# Pai_zhen_Pin.net
KiCad netlist of a schematic drawn in EasyEDA Pro
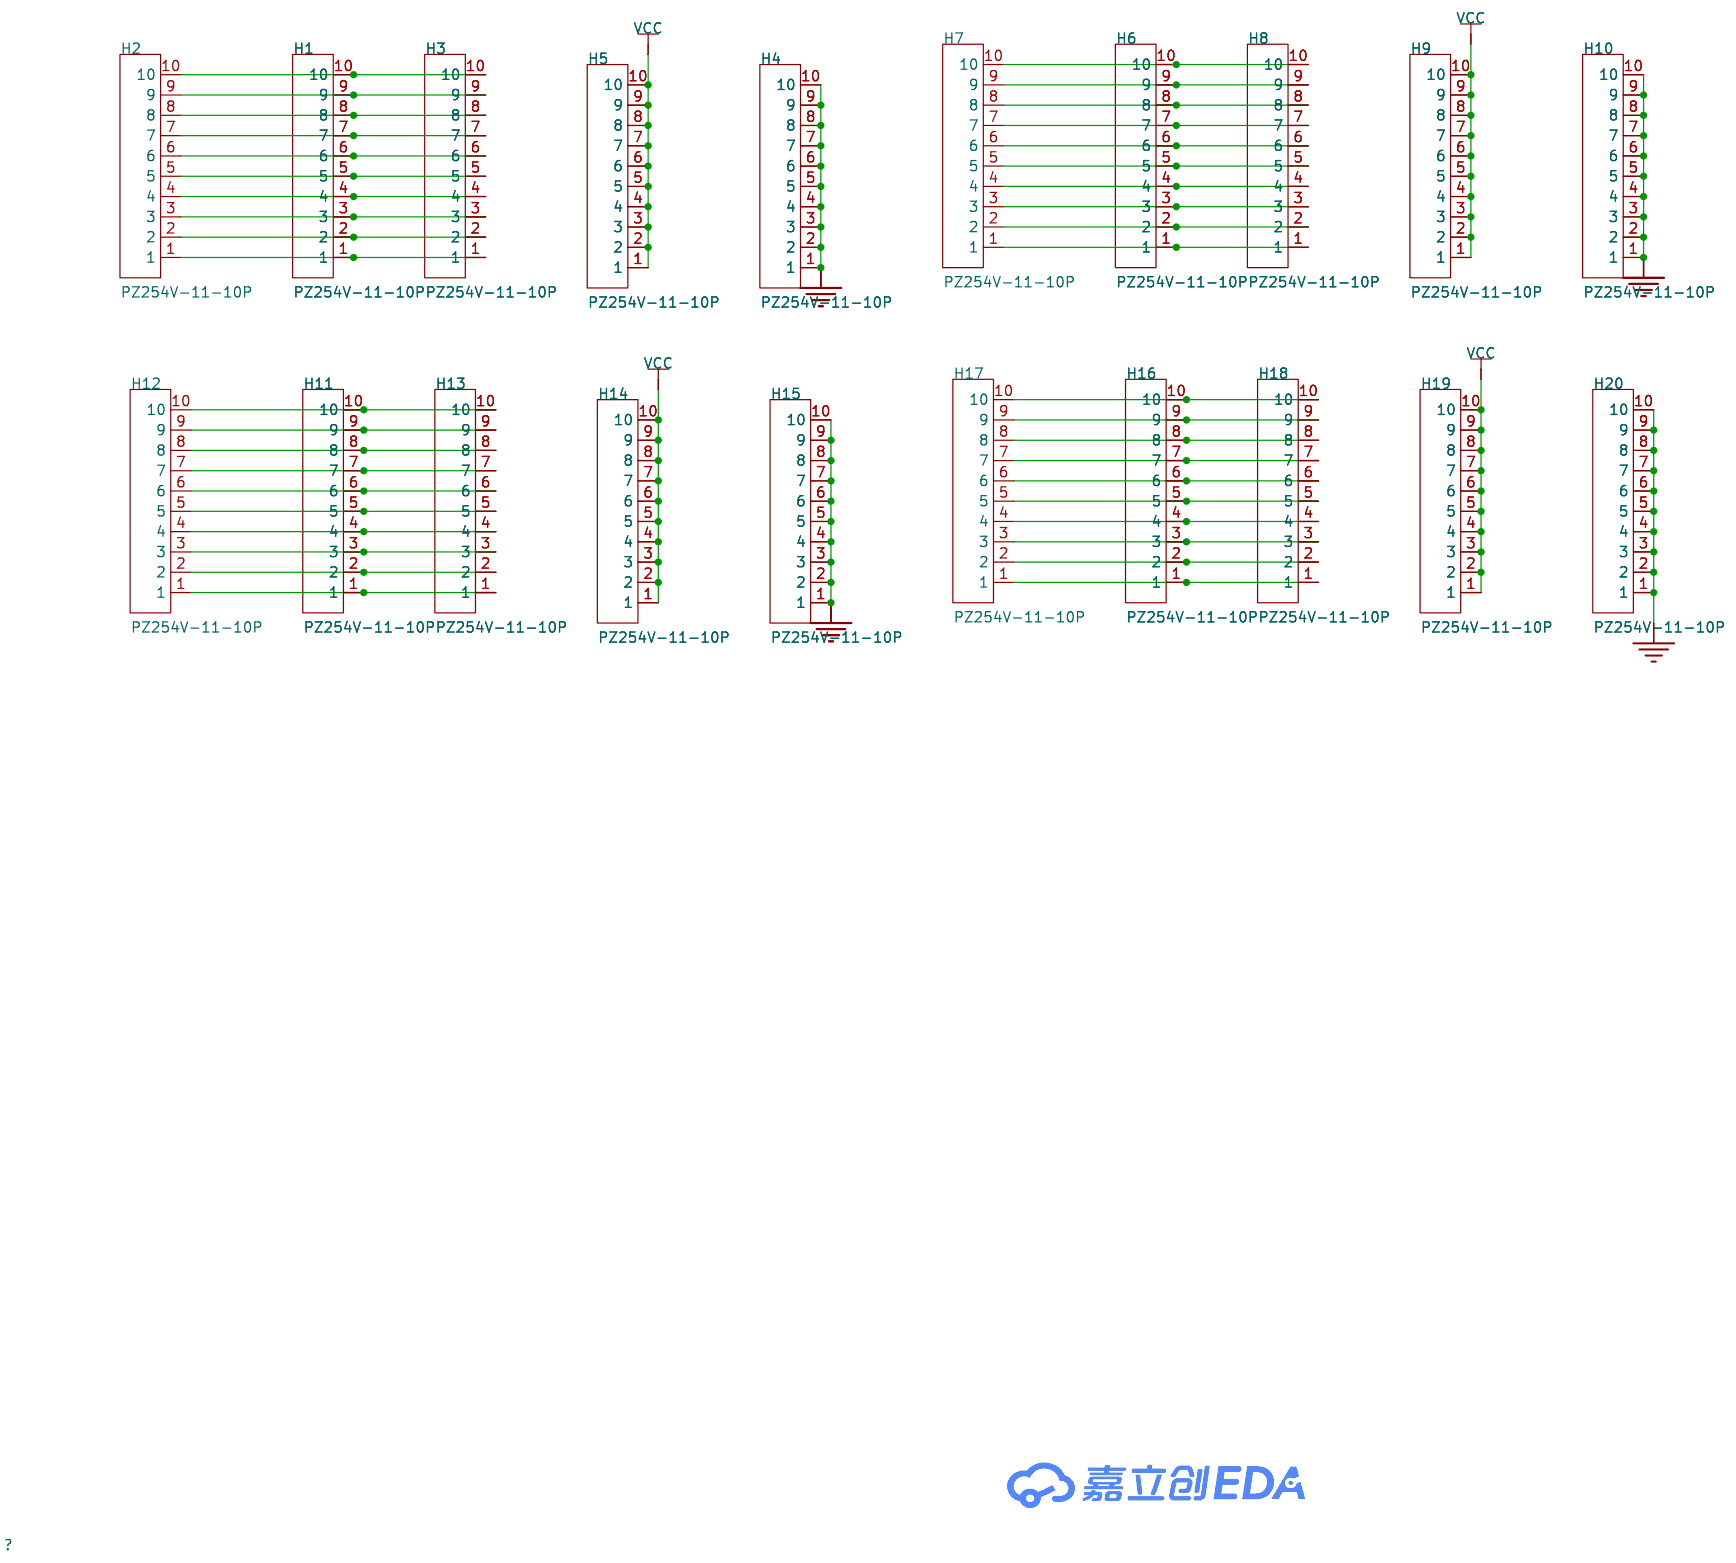
[diagram p0: schematic sheet]

(export (version "E")
  (design (tool "Eeschema 10.0.6"))
  (components
    (comp (ref "H1")
      (value "PZ254V-11-10P")
      (footprint "easyedapro:HDR-TH_10P-P2.54-V-M")
      (fields (field (name "Manufacturer") "XFCN(兴飞)"))
      (libsource (lib "easyedapro") (part "PZ254V-11-10P"))
    )
    (comp (ref "H2")
      (value "PZ254V-11-10P")
      (footprint "easyedapro:HDR-TH_10P-P2.54-V-M")
      (fields (field (name "Manufacturer") "XFCN(兴飞)"))
      (libsource (lib "easyedapro") (part "PZ254V-11-10P"))
    )
    (comp (ref "H3")
      (value "PZ254V-11-10P")
      (footprint "easyedapro:HDR-TH_10P-P2.54-V-M")
      (fields (field (name "Manufacturer") "XFCN(兴飞)"))
      (libsource (lib "easyedapro") (part "PZ254V-11-10P"))
    )
    (comp (ref "H4")
      (value "PZ254V-11-10P")
      (footprint "easyedapro:HDR-TH_10P-P2.54-V-M")
      (fields (field (name "Manufacturer") "XFCN(兴飞)"))
      (libsource (lib "easyedapro") (part "PZ254V-11-10P"))
    )
    (comp (ref "H5")
      (value "PZ254V-11-10P")
      (footprint "easyedapro:HDR-TH_10P-P2.54-V-M")
      (fields (field (name "Manufacturer") "XFCN(兴飞)"))
      (libsource (lib "easyedapro") (part "PZ254V-11-10P"))
    )
    (comp (ref "H6")
      (value "PZ254V-11-10P")
      (footprint "easyedapro:HDR-TH_10P-P2.54-V-M")
      (fields (field (name "Manufacturer") "XFCN(兴飞)"))
      (libsource (lib "easyedapro") (part "PZ254V-11-10P"))
    )
    (comp (ref "H7")
      (value "PZ254V-11-10P")
      (footprint "easyedapro:HDR-TH_10P-P2.54-V-M")
      (fields (field (name "Manufacturer") "XFCN(兴飞)"))
      (libsource (lib "easyedapro") (part "PZ254V-11-10P"))
    )
    (comp (ref "H8")
      (value "PZ254V-11-10P")
      (footprint "easyedapro:HDR-TH_10P-P2.54-V-M")
      (fields (field (name "Manufacturer") "XFCN(兴飞)"))
      (libsource (lib "easyedapro") (part "PZ254V-11-10P"))
    )
    (comp (ref "H9")
      (value "PZ254V-11-10P")
      (footprint "easyedapro:HDR-TH_10P-P2.54-V-M")
      (fields (field (name "Manufacturer") "XFCN(兴飞)"))
      (libsource (lib "easyedapro") (part "PZ254V-11-10P"))
    )
    (comp (ref "H10")
      (value "PZ254V-11-10P")
      (footprint "easyedapro:HDR-TH_10P-P2.54-V-M")
      (fields (field (name "Manufacturer") "XFCN(兴飞)"))
      (libsource (lib "easyedapro") (part "PZ254V-11-10P"))
    )
    (comp (ref "H11")
      (value "PZ254V-11-10P")
      (footprint "easyedapro:HDR-TH_10P-P2.54-V-M")
      (fields (field (name "Manufacturer") "XFCN(兴飞)"))
      (libsource (lib "easyedapro") (part "PZ254V-11-10P"))
    )
    (comp (ref "H12")
      (value "PZ254V-11-10P")
      (footprint "easyedapro:HDR-TH_10P-P2.54-V-M")
      (fields (field (name "Manufacturer") "XFCN(兴飞)"))
      (libsource (lib "easyedapro") (part "PZ254V-11-10P"))
    )
    (comp (ref "H13")
      (value "PZ254V-11-10P")
      (footprint "easyedapro:HDR-TH_10P-P2.54-V-M")
      (fields (field (name "Manufacturer") "XFCN(兴飞)"))
      (libsource (lib "easyedapro") (part "PZ254V-11-10P"))
    )
    (comp (ref "H14")
      (value "PZ254V-11-10P")
      (footprint "easyedapro:HDR-TH_10P-P2.54-V-M")
      (fields (field (name "Manufacturer") "XFCN(兴飞)"))
      (libsource (lib "easyedapro") (part "PZ254V-11-10P"))
    )
    (comp (ref "H15")
      (value "PZ254V-11-10P")
      (footprint "easyedapro:HDR-TH_10P-P2.54-V-M")
      (fields (field (name "Manufacturer") "XFCN(兴飞)"))
      (libsource (lib "easyedapro") (part "PZ254V-11-10P"))
    )
    (comp (ref "H16")
      (value "PZ254V-11-10P")
      (footprint "easyedapro:HDR-TH_10P-P2.54-V-M")
      (fields (field (name "Manufacturer") "XFCN(兴飞)"))
      (libsource (lib "easyedapro") (part "PZ254V-11-10P"))
    )
    (comp (ref "H17")
      (value "PZ254V-11-10P")
      (footprint "easyedapro:HDR-TH_10P-P2.54-V-M")
      (fields (field (name "Manufacturer") "XFCN(兴飞)"))
      (libsource (lib "easyedapro") (part "PZ254V-11-10P"))
    )
    (comp (ref "H18")
      (value "PZ254V-11-10P")
      (footprint "easyedapro:HDR-TH_10P-P2.54-V-M")
      (fields (field (name "Manufacturer") "XFCN(兴飞)"))
      (libsource (lib "easyedapro") (part "PZ254V-11-10P"))
    )
    (comp (ref "H19")
      (value "PZ254V-11-10P")
      (footprint "easyedapro:HDR-TH_10P-P2.54-V-M")
      (fields (field (name "Manufacturer") "XFCN(兴飞)"))
      (libsource (lib "easyedapro") (part "PZ254V-11-10P"))
    )
    (comp (ref "H20")
      (value "PZ254V-11-10P")
      (footprint "easyedapro:HDR-TH_10P-P2.54-V-M")
      (fields (field (name "Manufacturer") "XFCN(兴飞)"))
      (libsource (lib "easyedapro") (part "PZ254V-11-10P"))
    )
  )
  (nets
    (net (code "1") (name "GND") (class "Default")
      (node (ref "H10") (pin "1") (pinfunction "1_1") (pintype "unspecified"))
      (node (ref "H10") (pin "10") (pinfunction "10_10") (pintype "unspecified"))
      (node (ref "H10") (pin "2") (pinfunction "2_2") (pintype "unspecified"))
      (node (ref "H10") (pin "3") (pinfunction "3_3") (pintype "unspecified"))
      (node (ref "H10") (pin "4") (pinfunction "4_4") (pintype "unspecified"))
      (node (ref "H10") (pin "5") (pinfunction "5_5") (pintype "unspecified"))
      (node (ref "H10") (pin "6") (pinfunction "6_6") (pintype "unspecified"))
      (node (ref "H10") (pin "7") (pinfunction "7_7") (pintype "unspecified"))
      (node (ref "H10") (pin "8") (pinfunction "8_8") (pintype "unspecified"))
      (node (ref "H10") (pin "9") (pinfunction "9_9") (pintype "unspecified"))
      (node (ref "H15") (pin "1") (pinfunction "1_1") (pintype "unspecified"))
      (node (ref "H15") (pin "10") (pinfunction "10_10") (pintype "unspecified"))
      (node (ref "H15") (pin "2") (pinfunction "2_2") (pintype "unspecified"))
      (node (ref "H15") (pin "3") (pinfunction "3_3") (pintype "unspecified"))
      (node (ref "H15") (pin "4") (pinfunction "4_4") (pintype "unspecified"))
      (node (ref "H15") (pin "5") (pinfunction "5_5") (pintype "unspecified"))
      (node (ref "H15") (pin "6") (pinfunction "6_6") (pintype "unspecified"))
      (node (ref "H15") (pin "7") (pinfunction "7_7") (pintype "unspecified"))
      (node (ref "H15") (pin "8") (pinfunction "8_8") (pintype "unspecified"))
      (node (ref "H15") (pin "9") (pinfunction "9_9") (pintype "unspecified"))
      (node (ref "H20") (pin "1") (pinfunction "1_1") (pintype "unspecified"))
      (node (ref "H20") (pin "10") (pinfunction "10_10") (pintype "unspecified"))
      (node (ref "H20") (pin "2") (pinfunction "2_2") (pintype "unspecified"))
      (node (ref "H20") (pin "3") (pinfunction "3_3") (pintype "unspecified"))
      (node (ref "H20") (pin "4") (pinfunction "4_4") (pintype "unspecified"))
      (node (ref "H20") (pin "5") (pinfunction "5_5") (pintype "unspecified"))
      (node (ref "H20") (pin "6") (pinfunction "6_6") (pintype "unspecified"))
      (node (ref "H20") (pin "7") (pinfunction "7_7") (pintype "unspecified"))
      (node (ref "H20") (pin "8") (pinfunction "8_8") (pintype "unspecified"))
      (node (ref "H20") (pin "9") (pinfunction "9_9") (pintype "unspecified"))
      (node (ref "H4") (pin "1") (pinfunction "1_1") (pintype "unspecified"))
      (node (ref "H4") (pin "10") (pinfunction "10_10") (pintype "unspecified"))
      (node (ref "H4") (pin "2") (pinfunction "2_2") (pintype "unspecified"))
      (node (ref "H4") (pin "3") (pinfunction "3_3") (pintype "unspecified"))
      (node (ref "H4") (pin "4") (pinfunction "4_4") (pintype "unspecified"))
      (node (ref "H4") (pin "5") (pinfunction "5_5") (pintype "unspecified"))
      (node (ref "H4") (pin "6") (pinfunction "6_6") (pintype "unspecified"))
      (node (ref "H4") (pin "7") (pinfunction "7_7") (pintype "unspecified"))
      (node (ref "H4") (pin "8") (pinfunction "8_8") (pintype "unspecified"))
      (node (ref "H4") (pin "9") (pinfunction "9_9") (pintype "unspecified"))
    )
    (net (code "2") (name "Net-(H1-Pad1)") (class "Default")
      (node (ref "H1") (pin "1") (pinfunction "1_1") (pintype "unspecified"))
      (node (ref "H2") (pin "1") (pinfunction "1_1") (pintype "unspecified"))
      (node (ref "H3") (pin "1") (pinfunction "1_1") (pintype "unspecified"))
    )
    (net (code "3") (name "Net-(H1-Pad2)") (class "Default")
      (node (ref "H1") (pin "2") (pinfunction "2_2") (pintype "unspecified"))
      (node (ref "H2") (pin "2") (pinfunction "2_2") (pintype "unspecified"))
      (node (ref "H3") (pin "2") (pinfunction "2_2") (pintype "unspecified"))
    )
    (net (code "4") (name "Net-(H1-Pad3)") (class "Default")
      (node (ref "H1") (pin "3") (pinfunction "3_3") (pintype "unspecified"))
      (node (ref "H2") (pin "3") (pinfunction "3_3") (pintype "unspecified"))
      (node (ref "H3") (pin "3") (pinfunction "3_3") (pintype "unspecified"))
    )
    (net (code "5") (name "Net-(H1-Pad4)") (class "Default")
      (node (ref "H1") (pin "4") (pinfunction "4_4") (pintype "unspecified"))
      (node (ref "H2") (pin "4") (pinfunction "4_4") (pintype "unspecified"))
      (node (ref "H3") (pin "4") (pinfunction "4_4") (pintype "unspecified"))
    )
    (net (code "6") (name "Net-(H1-Pad5)") (class "Default")
      (node (ref "H1") (pin "5") (pinfunction "5_5") (pintype "unspecified"))
      (node (ref "H2") (pin "5") (pinfunction "5_5") (pintype "unspecified"))
      (node (ref "H3") (pin "5") (pinfunction "5_5") (pintype "unspecified"))
    )
    (net (code "7") (name "Net-(H1-Pad6)") (class "Default")
      (node (ref "H1") (pin "6") (pinfunction "6_6") (pintype "unspecified"))
      (node (ref "H2") (pin "6") (pinfunction "6_6") (pintype "unspecified"))
      (node (ref "H3") (pin "6") (pinfunction "6_6") (pintype "unspecified"))
    )
    (net (code "8") (name "Net-(H1-Pad7)") (class "Default")
      (node (ref "H1") (pin "7") (pinfunction "7_7") (pintype "unspecified"))
      (node (ref "H2") (pin "7") (pinfunction "7_7") (pintype "unspecified"))
      (node (ref "H3") (pin "7") (pinfunction "7_7") (pintype "unspecified"))
    )
    (net (code "9") (name "Net-(H1-Pad8)") (class "Default")
      (node (ref "H1") (pin "8") (pinfunction "8_8") (pintype "unspecified"))
      (node (ref "H2") (pin "8") (pinfunction "8_8") (pintype "unspecified"))
      (node (ref "H3") (pin "8") (pinfunction "8_8") (pintype "unspecified"))
    )
    (net (code "10") (name "Net-(H1-Pad9)") (class "Default")
      (node (ref "H1") (pin "9") (pinfunction "9_9") (pintype "unspecified"))
      (node (ref "H2") (pin "9") (pinfunction "9_9") (pintype "unspecified"))
      (node (ref "H3") (pin "9") (pinfunction "9_9") (pintype "unspecified"))
    )
    (net (code "11") (name "Net-(H1-Pad10)") (class "Default")
      (node (ref "H1") (pin "10") (pinfunction "10_10") (pintype "unspecified"))
      (node (ref "H2") (pin "10") (pinfunction "10_10") (pintype "unspecified"))
      (node (ref "H3") (pin "10") (pinfunction "10_10") (pintype "unspecified"))
    )
    (net (code "12") (name "Net-(H6-Pad1)") (class "Default")
      (node (ref "H6") (pin "1") (pinfunction "1_1") (pintype "unspecified"))
      (node (ref "H7") (pin "1") (pinfunction "1_1") (pintype "unspecified"))
      (node (ref "H8") (pin "1") (pinfunction "1_1") (pintype "unspecified"))
    )
    (net (code "13") (name "Net-(H6-Pad2)") (class "Default")
      (node (ref "H6") (pin "2") (pinfunction "2_2") (pintype "unspecified"))
      (node (ref "H7") (pin "2") (pinfunction "2_2") (pintype "unspecified"))
      (node (ref "H8") (pin "2") (pinfunction "2_2") (pintype "unspecified"))
    )
    (net (code "14") (name "Net-(H6-Pad3)") (class "Default")
      (node (ref "H6") (pin "3") (pinfunction "3_3") (pintype "unspecified"))
      (node (ref "H7") (pin "3") (pinfunction "3_3") (pintype "unspecified"))
      (node (ref "H8") (pin "3") (pinfunction "3_3") (pintype "unspecified"))
    )
    (net (code "15") (name "Net-(H6-Pad4)") (class "Default")
      (node (ref "H6") (pin "4") (pinfunction "4_4") (pintype "unspecified"))
      (node (ref "H7") (pin "4") (pinfunction "4_4") (pintype "unspecified"))
      (node (ref "H8") (pin "4") (pinfunction "4_4") (pintype "unspecified"))
    )
    (net (code "16") (name "Net-(H6-Pad5)") (class "Default")
      (node (ref "H6") (pin "5") (pinfunction "5_5") (pintype "unspecified"))
      (node (ref "H7") (pin "5") (pinfunction "5_5") (pintype "unspecified"))
      (node (ref "H8") (pin "5") (pinfunction "5_5") (pintype "unspecified"))
    )
    (net (code "17") (name "Net-(H6-Pad6)") (class "Default")
      (node (ref "H6") (pin "6") (pinfunction "6_6") (pintype "unspecified"))
      (node (ref "H7") (pin "6") (pinfunction "6_6") (pintype "unspecified"))
      (node (ref "H8") (pin "6") (pinfunction "6_6") (pintype "unspecified"))
    )
    (net (code "18") (name "Net-(H6-Pad7)") (class "Default")
      (node (ref "H6") (pin "7") (pinfunction "7_7") (pintype "unspecified"))
      (node (ref "H7") (pin "7") (pinfunction "7_7") (pintype "unspecified"))
      (node (ref "H8") (pin "7") (pinfunction "7_7") (pintype "unspecified"))
    )
    (net (code "19") (name "Net-(H6-Pad8)") (class "Default")
      (node (ref "H6") (pin "8") (pinfunction "8_8") (pintype "unspecified"))
      (node (ref "H7") (pin "8") (pinfunction "8_8") (pintype "unspecified"))
      (node (ref "H8") (pin "8") (pinfunction "8_8") (pintype "unspecified"))
    )
    (net (code "20") (name "Net-(H6-Pad9)") (class "Default")
      (node (ref "H6") (pin "9") (pinfunction "9_9") (pintype "unspecified"))
      (node (ref "H7") (pin "9") (pinfunction "9_9") (pintype "unspecified"))
      (node (ref "H8") (pin "9") (pinfunction "9_9") (pintype "unspecified"))
    )
    (net (code "21") (name "Net-(H6-Pad10)") (class "Default")
      (node (ref "H6") (pin "10") (pinfunction "10_10") (pintype "unspecified"))
      (node (ref "H7") (pin "10") (pinfunction "10_10") (pintype "unspecified"))
      (node (ref "H8") (pin "10") (pinfunction "10_10") (pintype "unspecified"))
    )
    (net (code "22") (name "Net-(H11-Pad1)") (class "Default")
      (node (ref "H11") (pin "1") (pinfunction "1_1") (pintype "unspecified"))
      (node (ref "H12") (pin "1") (pinfunction "1_1") (pintype "unspecified"))
      (node (ref "H13") (pin "1") (pinfunction "1_1") (pintype "unspecified"))
    )
    (net (code "23") (name "Net-(H11-Pad2)") (class "Default")
      (node (ref "H11") (pin "2") (pinfunction "2_2") (pintype "unspecified"))
      (node (ref "H12") (pin "2") (pinfunction "2_2") (pintype "unspecified"))
      (node (ref "H13") (pin "2") (pinfunction "2_2") (pintype "unspecified"))
    )
    (net (code "24") (name "Net-(H11-Pad3)") (class "Default")
      (node (ref "H11") (pin "3") (pinfunction "3_3") (pintype "unspecified"))
      (node (ref "H12") (pin "3") (pinfunction "3_3") (pintype "unspecified"))
      (node (ref "H13") (pin "3") (pinfunction "3_3") (pintype "unspecified"))
    )
    (net (code "25") (name "Net-(H11-Pad4)") (class "Default")
      (node (ref "H11") (pin "4") (pinfunction "4_4") (pintype "unspecified"))
      (node (ref "H12") (pin "4") (pinfunction "4_4") (pintype "unspecified"))
      (node (ref "H13") (pin "4") (pinfunction "4_4") (pintype "unspecified"))
    )
    (net (code "26") (name "Net-(H11-Pad5)") (class "Default")
      (node (ref "H11") (pin "5") (pinfunction "5_5") (pintype "unspecified"))
      (node (ref "H12") (pin "5") (pinfunction "5_5") (pintype "unspecified"))
      (node (ref "H13") (pin "5") (pinfunction "5_5") (pintype "unspecified"))
    )
    (net (code "27") (name "Net-(H11-Pad6)") (class "Default")
      (node (ref "H11") (pin "6") (pinfunction "6_6") (pintype "unspecified"))
      (node (ref "H12") (pin "6") (pinfunction "6_6") (pintype "unspecified"))
      (node (ref "H13") (pin "6") (pinfunction "6_6") (pintype "unspecified"))
    )
    (net (code "28") (name "Net-(H11-Pad7)") (class "Default")
      (node (ref "H11") (pin "7") (pinfunction "7_7") (pintype "unspecified"))
      (node (ref "H12") (pin "7") (pinfunction "7_7") (pintype "unspecified"))
      (node (ref "H13") (pin "7") (pinfunction "7_7") (pintype "unspecified"))
    )
    (net (code "29") (name "Net-(H11-Pad8)") (class "Default")
      (node (ref "H11") (pin "8") (pinfunction "8_8") (pintype "unspecified"))
      (node (ref "H12") (pin "8") (pinfunction "8_8") (pintype "unspecified"))
      (node (ref "H13") (pin "8") (pinfunction "8_8") (pintype "unspecified"))
    )
    (net (code "30") (name "Net-(H11-Pad9)") (class "Default")
      (node (ref "H11") (pin "9") (pinfunction "9_9") (pintype "unspecified"))
      (node (ref "H12") (pin "9") (pinfunction "9_9") (pintype "unspecified"))
      (node (ref "H13") (pin "9") (pinfunction "9_9") (pintype "unspecified"))
    )
    (net (code "31") (name "Net-(H11-Pad10)") (class "Default")
      (node (ref "H11") (pin "10") (pinfunction "10_10") (pintype "unspecified"))
      (node (ref "H12") (pin "10") (pinfunction "10_10") (pintype "unspecified"))
      (node (ref "H13") (pin "10") (pinfunction "10_10") (pintype "unspecified"))
    )
    (net (code "32") (name "Net-(H16-Pad1)") (class "Default")
      (node (ref "H16") (pin "1") (pinfunction "1_1") (pintype "unspecified"))
      (node (ref "H17") (pin "1") (pinfunction "1_1") (pintype "unspecified"))
      (node (ref "H18") (pin "1") (pinfunction "1_1") (pintype "unspecified"))
    )
    (net (code "33") (name "Net-(H16-Pad2)") (class "Default")
      (node (ref "H16") (pin "2") (pinfunction "2_2") (pintype "unspecified"))
      (node (ref "H17") (pin "2") (pinfunction "2_2") (pintype "unspecified"))
      (node (ref "H18") (pin "2") (pinfunction "2_2") (pintype "unspecified"))
    )
    (net (code "34") (name "Net-(H16-Pad3)") (class "Default")
      (node (ref "H16") (pin "3") (pinfunction "3_3") (pintype "unspecified"))
      (node (ref "H17") (pin "3") (pinfunction "3_3") (pintype "unspecified"))
      (node (ref "H18") (pin "3") (pinfunction "3_3") (pintype "unspecified"))
    )
    (net (code "35") (name "Net-(H16-Pad4)") (class "Default")
      (node (ref "H16") (pin "4") (pinfunction "4_4") (pintype "unspecified"))
      (node (ref "H17") (pin "4") (pinfunction "4_4") (pintype "unspecified"))
      (node (ref "H18") (pin "4") (pinfunction "4_4") (pintype "unspecified"))
    )
    (net (code "36") (name "Net-(H16-Pad5)") (class "Default")
      (node (ref "H16") (pin "5") (pinfunction "5_5") (pintype "unspecified"))
      (node (ref "H17") (pin "5") (pinfunction "5_5") (pintype "unspecified"))
      (node (ref "H18") (pin "5") (pinfunction "5_5") (pintype "unspecified"))
    )
    (net (code "37") (name "Net-(H16-Pad6)") (class "Default")
      (node (ref "H16") (pin "6") (pinfunction "6_6") (pintype "unspecified"))
      (node (ref "H17") (pin "6") (pinfunction "6_6") (pintype "unspecified"))
      (node (ref "H18") (pin "6") (pinfunction "6_6") (pintype "unspecified"))
    )
    (net (code "38") (name "Net-(H16-Pad7)") (class "Default")
      (node (ref "H16") (pin "7") (pinfunction "7_7") (pintype "unspecified"))
      (node (ref "H17") (pin "7") (pinfunction "7_7") (pintype "unspecified"))
      (node (ref "H18") (pin "7") (pinfunction "7_7") (pintype "unspecified"))
    )
    (net (code "39") (name "Net-(H16-Pad8)") (class "Default")
      (node (ref "H16") (pin "8") (pinfunction "8_8") (pintype "unspecified"))
      (node (ref "H17") (pin "8") (pinfunction "8_8") (pintype "unspecified"))
      (node (ref "H18") (pin "8") (pinfunction "8_8") (pintype "unspecified"))
    )
    (net (code "40") (name "Net-(H16-Pad9)") (class "Default")
      (node (ref "H16") (pin "9") (pinfunction "9_9") (pintype "unspecified"))
      (node (ref "H17") (pin "9") (pinfunction "9_9") (pintype "unspecified"))
      (node (ref "H18") (pin "9") (pinfunction "9_9") (pintype "unspecified"))
    )
    (net (code "41") (name "Net-(H16-Pad10)") (class "Default")
      (node (ref "H16") (pin "10") (pinfunction "10_10") (pintype "unspecified"))
      (node (ref "H17") (pin "10") (pinfunction "10_10") (pintype "unspecified"))
      (node (ref "H18") (pin "10") (pinfunction "10_10") (pintype "unspecified"))
    )
    (net (code "42") (name "VCC") (class "Default")
      (node (ref "H14") (pin "1") (pinfunction "1_1") (pintype "unspecified"))
      (node (ref "H14") (pin "10") (pinfunction "10_10") (pintype "unspecified"))
      (node (ref "H14") (pin "2") (pinfunction "2_2") (pintype "unspecified"))
      (node (ref "H14") (pin "3") (pinfunction "3_3") (pintype "unspecified"))
      (node (ref "H14") (pin "4") (pinfunction "4_4") (pintype "unspecified"))
      (node (ref "H14") (pin "5") (pinfunction "5_5") (pintype "unspecified"))
      (node (ref "H14") (pin "6") (pinfunction "6_6") (pintype "unspecified"))
      (node (ref "H14") (pin "7") (pinfunction "7_7") (pintype "unspecified"))
      (node (ref "H14") (pin "8") (pinfunction "8_8") (pintype "unspecified"))
      (node (ref "H14") (pin "9") (pinfunction "9_9") (pintype "unspecified"))
      (node (ref "H19") (pin "1") (pinfunction "1_1") (pintype "unspecified"))
      (node (ref "H19") (pin "10") (pinfunction "10_10") (pintype "unspecified"))
      (node (ref "H19") (pin "2") (pinfunction "2_2") (pintype "unspecified"))
      (node (ref "H19") (pin "3") (pinfunction "3_3") (pintype "unspecified"))
      (node (ref "H19") (pin "4") (pinfunction "4_4") (pintype "unspecified"))
      (node (ref "H19") (pin "5") (pinfunction "5_5") (pintype "unspecified"))
      (node (ref "H19") (pin "6") (pinfunction "6_6") (pintype "unspecified"))
      (node (ref "H19") (pin "7") (pinfunction "7_7") (pintype "unspecified"))
      (node (ref "H19") (pin "8") (pinfunction "8_8") (pintype "unspecified"))
      (node (ref "H19") (pin "9") (pinfunction "9_9") (pintype "unspecified"))
      (node (ref "H5") (pin "1") (pinfunction "1_1") (pintype "unspecified"))
      (node (ref "H5") (pin "10") (pinfunction "10_10") (pintype "unspecified"))
      (node (ref "H5") (pin "2") (pinfunction "2_2") (pintype "unspecified"))
      (node (ref "H5") (pin "3") (pinfunction "3_3") (pintype "unspecified"))
      (node (ref "H5") (pin "4") (pinfunction "4_4") (pintype "unspecified"))
      (node (ref "H5") (pin "5") (pinfunction "5_5") (pintype "unspecified"))
      (node (ref "H5") (pin "6") (pinfunction "6_6") (pintype "unspecified"))
      (node (ref "H5") (pin "7") (pinfunction "7_7") (pintype "unspecified"))
      (node (ref "H5") (pin "8") (pinfunction "8_8") (pintype "unspecified"))
      (node (ref "H5") (pin "9") (pinfunction "9_9") (pintype "unspecified"))
      (node (ref "H9") (pin "1") (pinfunction "1_1") (pintype "unspecified"))
      (node (ref "H9") (pin "10") (pinfunction "10_10") (pintype "unspecified"))
      (node (ref "H9") (pin "2") (pinfunction "2_2") (pintype "unspecified"))
      (node (ref "H9") (pin "3") (pinfunction "3_3") (pintype "unspecified"))
      (node (ref "H9") (pin "4") (pinfunction "4_4") (pintype "unspecified"))
      (node (ref "H9") (pin "5") (pinfunction "5_5") (pintype "unspecified"))
      (node (ref "H9") (pin "6") (pinfunction "6_6") (pintype "unspecified"))
      (node (ref "H9") (pin "7") (pinfunction "7_7") (pintype "unspecified"))
      (node (ref "H9") (pin "8") (pinfunction "8_8") (pintype "unspecified"))
      (node (ref "H9") (pin "9") (pinfunction "9_9") (pintype "unspecified"))
    )
  )
)
